# 01-POWER_AC-DC.net
KiCad netlist of a schematic drawn in Altium Designer
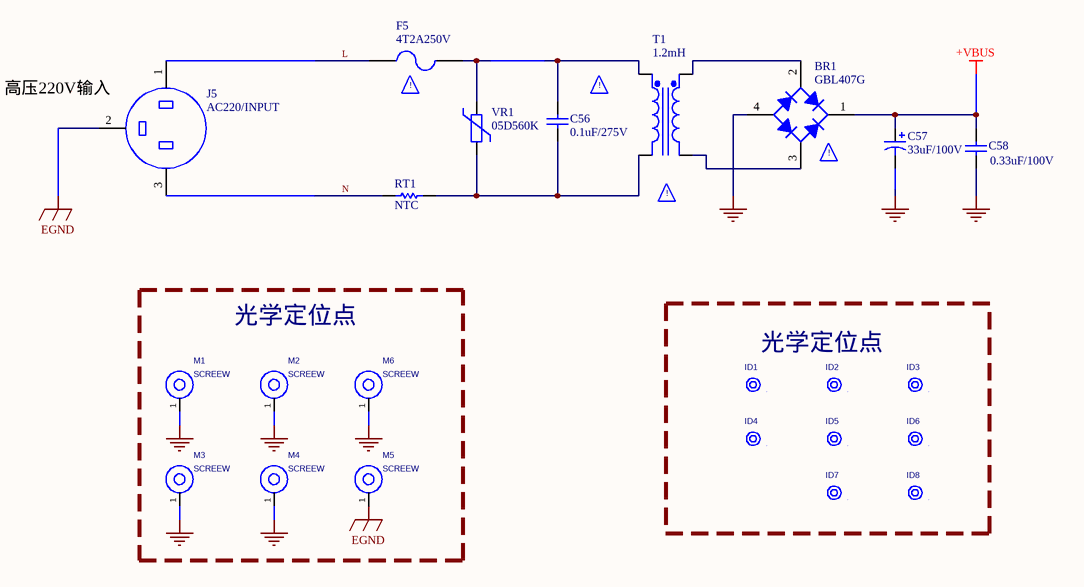
[diagram p0: 01-POWER AC-DC.SchDoc]

(export (version "E")
  (design (tool "Eeschema 10.0.6"))
  (components
    (comp (ref "BR1")
      (value "GBL407G")
      (footprint "GBL407G")
      (description "Full Wave Diode Bridge")
      (fields (field (name "ALTIUM_UNNAMED_1") "GBL407G") (field (name "PUBLISHER") "Altium Limited"))
      (libsource (lib "Miscellaneous Devices") (part "Bridge1"))
    )
    (comp (ref "C56")
      (value "0.1uF/275V")
      (footprint "CBB62-275VAC-104K")
      (description "Capacitor")
      (fields (field (name "Comment") "Cap") (field (name "PUBLISHER") "Altium Limited"))
      (libsource (lib "Miscellaneous Devices") (part "Cap"))
    )
    (comp (ref "C57")
      (value "33uF/100V")
      (footprint "CE16250SH1")
      (description "Polarized Capacitor (Radial)")
      (fields (field (name "PUBLISHER") "Altium Limited"))
      (libsource (lib "Miscellaneous Devices") (part "Cap Pol1"))
    )
    (comp (ref "C58")
      (value "0.33uF/100V")
      (footprint "AF334J1J079L270D9H")
      (description "Capacitor")
      (fields (field (name "Comment") "Cap") (field (name "PUBLISHER") "Altium Limited"))
      (libsource (lib "Miscellaneous Devices") (part "Cap"))
    )
    (comp (ref "F5")
      (value "Fuse 2")
      (footprint "4T2A250V")
      (description "Fuse")
      (fields (field (name "ALTIUM_UNNAMED_1") "4T2A250V") (field (name "PUBLISHER") "Altium Limited"))
      (libsource (lib "Miscellaneous Devices") (part "Fuse 2"))
    )
    (comp (ref "ID1")
      (value "LOC")
      (footprint "MARK_1")
      (description "SMT_Locotion")
      (libsource (lib "EMIA-2024-03") (part "LOC"))
    )
    (comp (ref "ID2")
      (value "LOC")
      (footprint "MARK_1")
      (description "SMT_Locotion")
      (libsource (lib "EMIA-2024-03") (part "LOC"))
    )
    (comp (ref "ID3")
      (value "LOC")
      (footprint "MARK_1")
      (description "SMT_Locotion")
      (libsource (lib "EMIA-2024-03") (part "LOC"))
    )
    (comp (ref "ID4")
      (value "LOC")
      (footprint "MARK_1")
      (description "SMT_Locotion")
      (libsource (lib "EMIA-2024-03") (part "LOC"))
    )
    (comp (ref "ID5")
      (value "LOC")
      (footprint "MARK_1")
      (description "SMT_Locotion")
      (libsource (lib "EMIA-2024-03") (part "LOC"))
    )
    (comp (ref "ID6")
      (value "LOC")
      (footprint "MARK_1")
      (description "SMT_Locotion")
      (libsource (lib "EMIA-2024-03") (part "LOC"))
    )
    (comp (ref "ID7")
      (value "LOC")
      (footprint "MARK_1")
      (description "SMT_Locotion")
      (libsource (lib "EMIA-2024-03") (part "LOC"))
    )
    (comp (ref "ID8")
      (value "LOC")
      (footprint "MARK_1")
      (description "SMT_Locotion")
      (libsource (lib "EMIA-2024-03") (part "LOC"))
    )
    (comp (ref "J5")
      (value "AC220/INPUT")
      (footprint "VH-3A")
      (libsource (lib "SCHLIB") (part "AC220/INPUT"))
    )
    (comp (ref "M1")
      (value "SCREEW")
      (footprint "SCREEW")
      (description "MARK Symble")
      (fields (field (name "Comment") "MARK_4") (field (name "CREATED_BY") "CZD"))
      (libsource (lib "*") (part "MARK_4"))
    )
    (comp (ref "M2")
      (value "SCREEW")
      (footprint "SCREEW")
      (description "MARK Symble")
      (fields (field (name "Comment") "MARK_4") (field (name "CREATED_BY") "CZD"))
      (libsource (lib "*") (part "MARK_4"))
    )
    (comp (ref "M3")
      (value "SCREEW")
      (footprint "SCREEW")
      (description "MARK Symble")
      (fields (field (name "Comment") "MARK_4") (field (name "CREATED_BY") "CZD"))
      (libsource (lib "*") (part "MARK_4"))
    )
    (comp (ref "M4")
      (value "SCREEW")
      (footprint "SCREEW")
      (description "MARK Symble")
      (fields (field (name "Comment") "MARK_4") (field (name "CREATED_BY") "CZD"))
      (libsource (lib "*") (part "MARK_4"))
    )
    (comp (ref "M5")
      (value "SCREEW")
      (footprint "SCREEW")
      (description "MARK Symble")
      (fields (field (name "Comment") "MARK_4") (field (name "CREATED_BY") "CZD"))
      (libsource (lib "*") (part "MARK_4"))
    )
    (comp (ref "M6")
      (value "SCREEW")
      (footprint "SCREEW")
      (description "MARK Symble")
      (fields (field (name "Comment") "MARK_4") (field (name "CREATED_BY") "CZD"))
      (libsource (lib "*") (part "MARK_4"))
    )
    (comp (ref "RT1")
      (value "NTC")
      (footprint "NTC-10D9")
      (description "Resistor")
      (fields (field (name "PUBLISHER") "Altium Limited"))
      (libsource (lib "Miscellaneous Devices") (part "Res1"))
    )
    (comp (ref "T1")
      (value "1.2mH")
      (footprint "UU1014")
      (description "Transformer (Equivalent Circuit Model)")
      (fields (field (name "PUBLISHER") "Altium Limited"))
      (libsource (lib "Miscellaneous Devices") (part "Trans Eq"))
    )
    (comp (ref "VR1") (value "05D560K") (footprint "RUEF400") (libsource (lib "SCHLIB") (part "VR 561K")))
  )
  (nets
    (net (code "1") (name "+VBUS") (class "Default")
      (node (ref "BR1") (pin "1") (pinfunction "K_1") (pintype "passive"))
      (node (ref "C57") (pin "1") (pinfunction "1_1") (pintype "passive"))
      (node (ref "C58") (pin "2") (pinfunction "2_2") (pintype "passive"))
    )
    (net (code "2") (name "/L") (class "Default")
      (node (ref "F5") (pin "1") (pinfunction "1_1") (pintype "passive"))
      (node (ref "J5") (pin "1") (pinfunction "1_1") (pintype "passive"))
    )
    (net (code "3") (name "/N") (class "Default")
      (node (ref "J5") (pin "3") (pinfunction "2_3") (pintype "passive"))
      (node (ref "RT1") (pin "1") (pinfunction "1_1") (pintype "passive"))
    )
    (net (code "4") (name "EGND") (class "Default")
      (node (ref "J5") (pin "2") (pinfunction "3_2") (pintype "passive"))
      (node (ref "M5") (pin "1") (pinfunction "1_1") (pintype "passive"))
    )
    (net (code "5") (name "GND") (class "Default")
      (node (ref "BR1") (pin "4") (pinfunction "A_4") (pintype "passive"))
      (node (ref "C57") (pin "2") (pinfunction "2_2") (pintype "passive"))
      (node (ref "C58") (pin "1") (pinfunction "1_1") (pintype "passive"))
      (node (ref "M1") (pin "1") (pinfunction "1_1") (pintype "passive"))
      (node (ref "M2") (pin "1") (pinfunction "1_1") (pintype "passive"))
      (node (ref "M3") (pin "1") (pinfunction "1_1") (pintype "passive"))
      (node (ref "M4") (pin "1") (pinfunction "1_1") (pintype "passive"))
      (node (ref "M6") (pin "1") (pinfunction "1_1") (pintype "passive"))
    )
    (net (code "6") (name "Net-(T1-Pri+)") (class "Default")
      (node (ref "C56") (pin "1") (pinfunction "1_1") (pintype "passive"))
      (node (ref "F5") (pin "2") (pinfunction "2_2") (pintype "passive"))
      (node (ref "T1") (pin "1") (pinfunction "Pri+_1") (pintype "passive"))
      (node (ref "VR1") (pin "2") (pinfunction "2_2") (pintype "passive"))
    )
    (net (code "7") (name "Net-(T1-Pri-)") (class "Default")
      (node (ref "C56") (pin "2") (pinfunction "2_2") (pintype "passive"))
      (node (ref "RT1") (pin "2") (pinfunction "2_2") (pintype "passive"))
      (node (ref "T1") (pin "2") (pinfunction "Pri-_2") (pintype "passive"))
      (node (ref "VR1") (pin "1") (pinfunction "1_1") (pintype "passive"))
    )
    (net (code "8") (name "Net-(T1-Sec+)") (class "Default")
      (node (ref "BR1") (pin "2") (pinfunction "C_2") (pintype "passive"))
      (node (ref "T1") (pin "3") (pinfunction "Sec+_3") (pintype "passive"))
    )
    (net (code "9") (name "Net-(T1-Sec-)") (class "Default")
      (node (ref "BR1") (pin "3") (pinfunction "C_3") (pintype "passive"))
      (node (ref "T1") (pin "4") (pinfunction "Sec-_4") (pintype "passive"))
    )
    (net (code "10") (name "unconnected-(ID1-Pad1)") (class "Default")
      (node (ref "ID1") (pin "1") (pinfunction "1_1") (pintype "passive"))
    )
    (net (code "11") (name "unconnected-(ID2-Pad1)") (class "Default")
      (node (ref "ID2") (pin "1") (pinfunction "1_1") (pintype "passive"))
    )
    (net (code "12") (name "unconnected-(ID3-Pad1)") (class "Default")
      (node (ref "ID3") (pin "1") (pinfunction "1_1") (pintype "passive"))
    )
    (net (code "13") (name "unconnected-(ID4-Pad1)") (class "Default")
      (node (ref "ID4") (pin "1") (pinfunction "1_1") (pintype "passive"))
    )
    (net (code "14") (name "unconnected-(ID5-Pad1)") (class "Default")
      (node (ref "ID5") (pin "1") (pinfunction "1_1") (pintype "passive"))
    )
    (net (code "15") (name "unconnected-(ID6-Pad1)") (class "Default")
      (node (ref "ID6") (pin "1") (pinfunction "1_1") (pintype "passive"))
    )
    (net (code "16") (name "unconnected-(ID7-Pad1)") (class "Default")
      (node (ref "ID7") (pin "1") (pinfunction "1_1") (pintype "passive"))
    )
    (net (code "17") (name "unconnected-(ID8-Pad1)") (class "Default")
      (node (ref "ID8") (pin "1") (pinfunction "1_1") (pintype "passive"))
    )
  )
)
